# AFT05MS004.net
KiCad netlist of a schematic drawn in Altium Designer
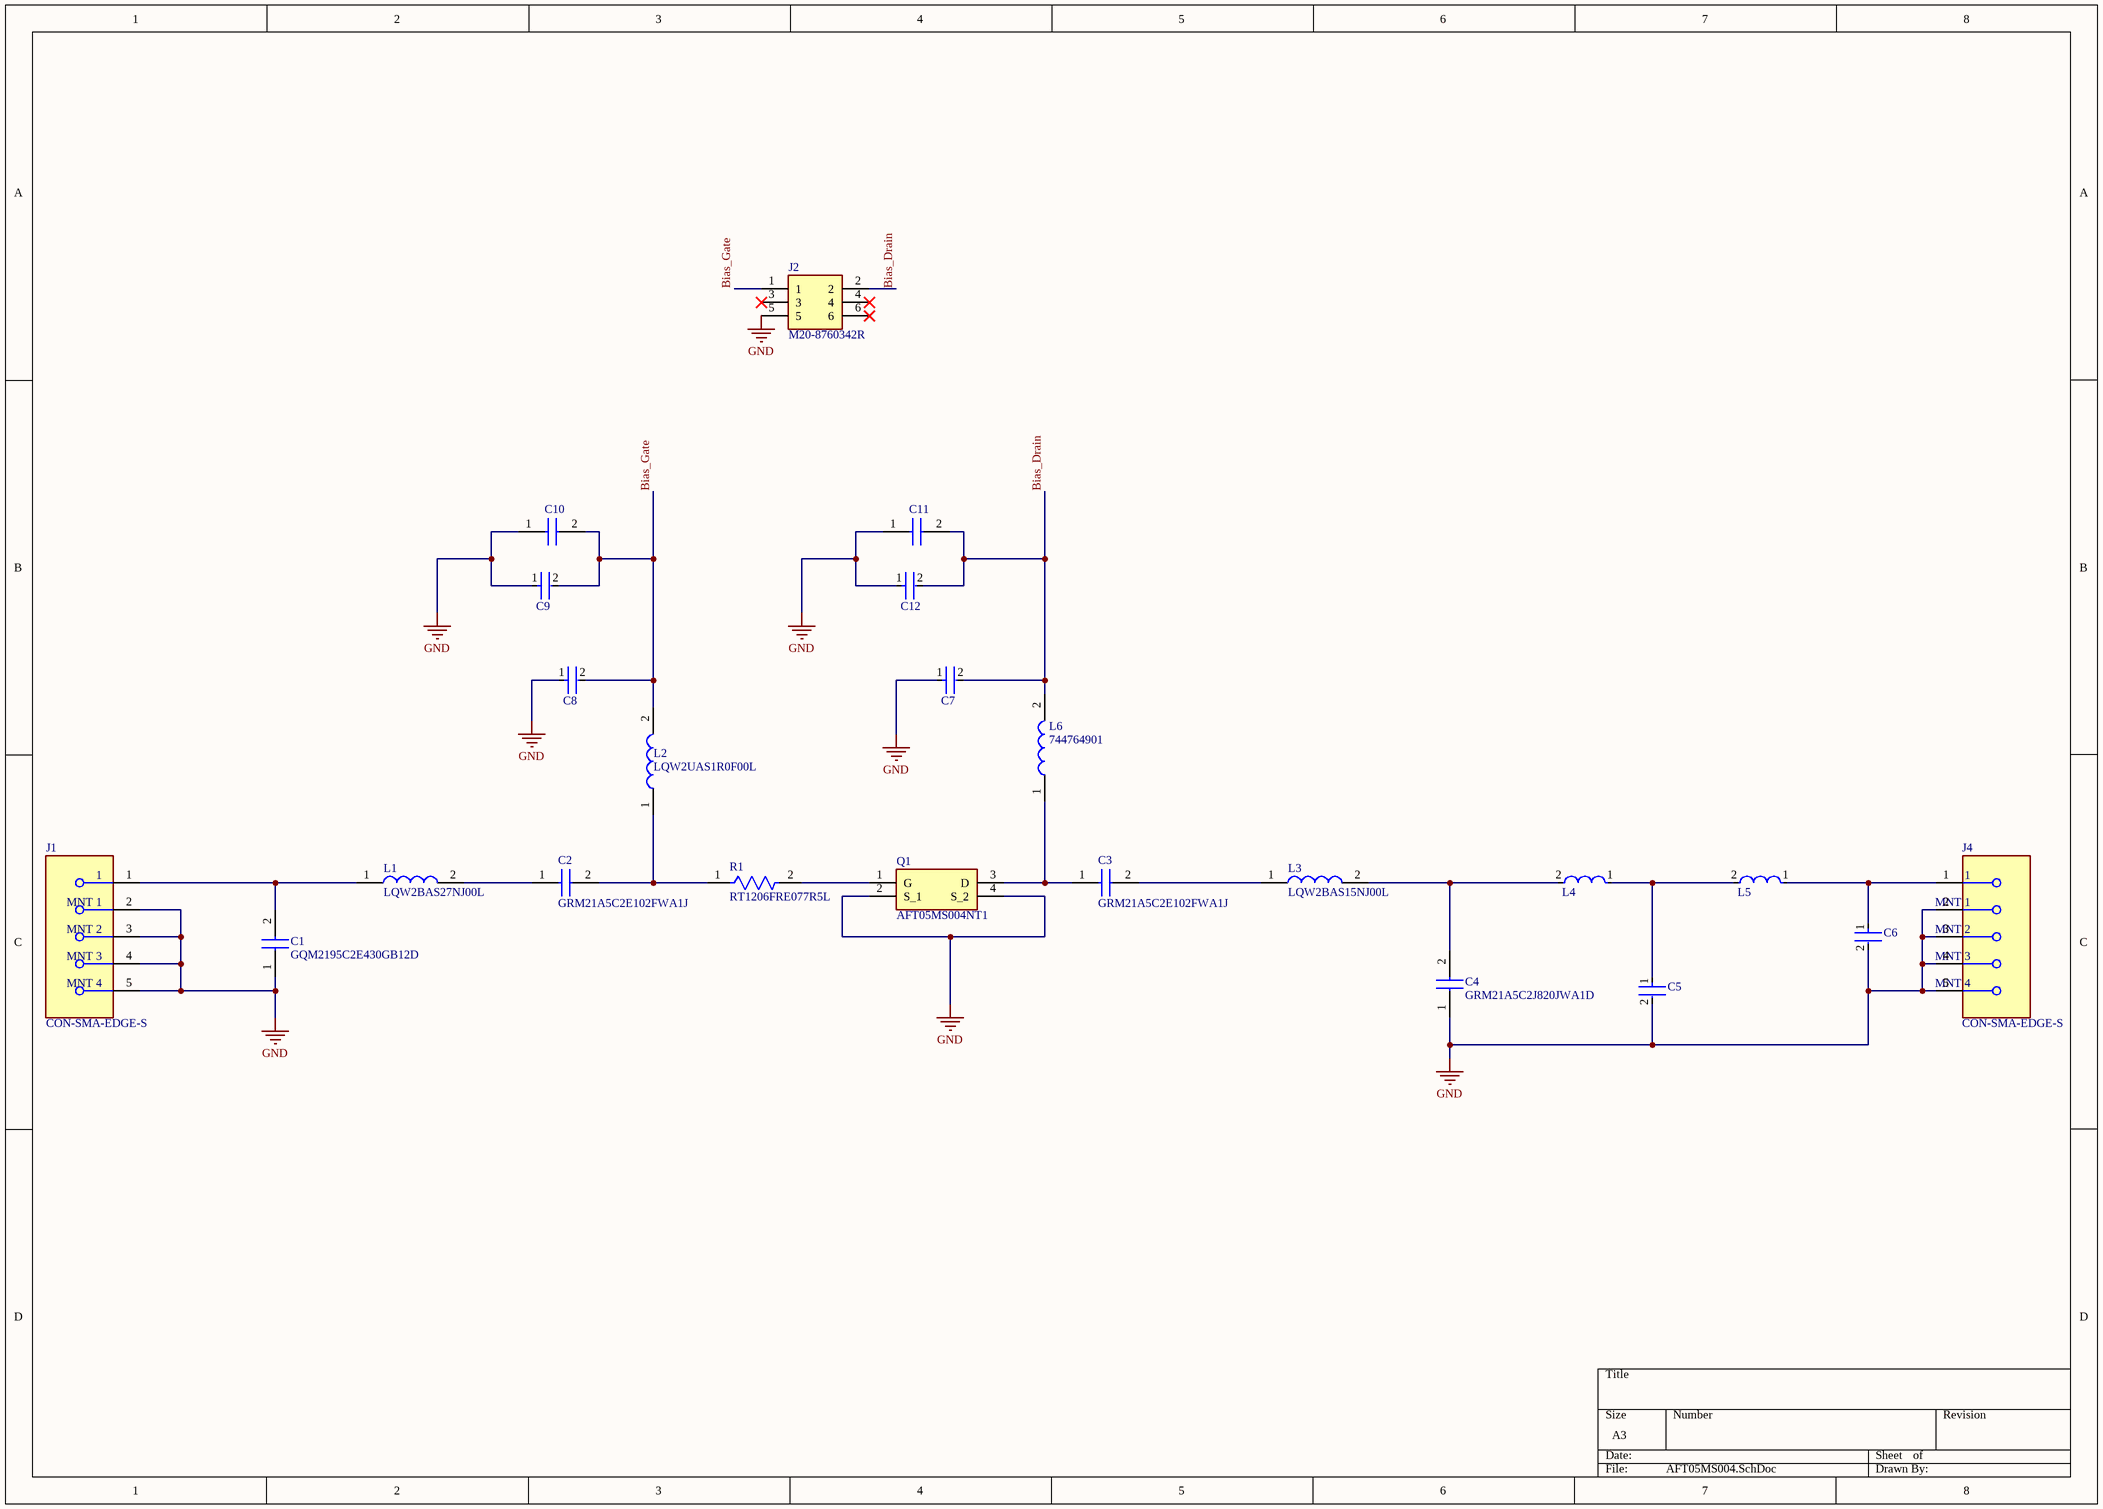
[diagram p0: AFT05MS004.SchDoc]

(export (version "E")
  (design (tool "Eeschema 10.0.6"))
  (components
    (comp (ref "C1")
      (value "GQM2195C2E430GB12D")
      (footprint "SamacSys:GQM2195C2E100GB12D")
      (description "Capacitor")
      (libsource (lib "*") (part "GQM2195C2E430GB12D"))
    )
    (comp (ref "C2")
      (value "GRM21A5C2E102FWA1J")
      (footprint "SamacSys:GRM21x")
      (description "Capacitor")
      (fields (field (name "MOUSER PART NUMBER") "81-GRM21A5C2E102FWA1"))
      (libsource (lib "*") (part "GRM21A5C2E102FWA1J"))
    )
    (comp (ref "C3")
      (value "GRM21A5C2E102FWA1J")
      (footprint "SamacSys:GRM21x")
      (description "Capacitor")
      (fields (field (name "MOUSER PART NUMBER") "81-GRM21A5C2E102FWA1"))
      (libsource (lib "*") (part "GRM21A5C2E102FWA1J"))
    )
    (comp (ref "C4")
      (value "GRM21A5C2J820JWA1D")
      (footprint "SamacSys:GRM21x")
      (description "Capacitor")
      (libsource (lib "*") (part "GRM21A5C2J820JWA1D"))
    )
    (comp (ref "C5")
      (value "GRM21A5C2E390FW01D")
      (footprint "FP-GRM21A-0_2-MFG")
      (description "Chip Multilayer Ceramic Capacitors for General Purpose, 0805, 1000pF, C0G, 30ppm/°C, 1%, 250V")
      (libsource (lib "Altium Content Vault") (part "02cd4be3c70576c341d710602a673aa"))
    )
    (comp (ref "C6")
      (value "GQM2195C2E300GB12D")
      (footprint "FP-GRM21A-0_2-MFG")
      (description "Chip Multilayer Ceramic Capacitors for General Purpose, 0805, 1000pF, C0G, 30ppm/°C, 1%, 250V")
      (libsource (lib "Altium Content Vault") (part "02cd4be3c70576c341d710602a673aa"))
    )
    (comp (ref "C7")
      (value "GQM2195C2E300GB12D")
      (footprint "FP-GRM21A-0_2-MFG")
      (description "Chip Multilayer Ceramic Capacitors for General Purpose, 0805, 1000pF, C0G, 30ppm/°C, 1%, 250V")
      (libsource (lib "Altium Content Vault") (part "02cd4be3c70576c341d710602a673aa"))
    )
    (comp (ref "C8")
      (value "GQM2195C2E300GB12D")
      (footprint "FP-GRM21A-0_2-MFG")
      (description "Chip Multilayer Ceramic Capacitors for General Purpose, 0805, 1000pF, C0G, 30ppm/°C, 1%, 250V")
      (libsource (lib "Altium Content Vault") (part "02cd4be3c70576c341d710602a673aa"))
    )
    (comp (ref "C9")
      (value "GRM21A5C2E102FWA1J")
      (footprint "FP-GRM21A-0_2-MFG")
      (description "Chip Multilayer Ceramic Capacitors for General Purpose, 0805, 1000pF, C0G, 30ppm/°C, 1%, 250V")
      (libsource (lib "Altium Content Vault") (part "02cd4be3c70576c341d710602a673aa"))
    )
    (comp (ref "C10")
      (value "GJ821BR71H105KA12K")
      (footprint "SamacSys:CAPC2012X135N")
      (description "Capacitor")
      (fields (field (name "MOUSER PART NUMBER") "81-GJ821BR71H105KA2K"))
      (libsource (lib "*") (part "GJ821BR71H105KA12K"))
    )
    (comp (ref "C11")
      (value "GJ821BR71H105KA12K")
      (footprint "SamacSys:CAPC2012X135N")
      (description "Capacitor")
      (fields (field (name "MOUSER PART NUMBER") "81-GJ821BR71H105KA2K"))
      (libsource (lib "*") (part "GJ821BR71H105KA12K"))
    )
    (comp (ref "C12")
      (value "GRM21A5C2E102FWA1J")
      (footprint "FP-GRM21A-0_2-MFG")
      (description "Chip Multilayer Ceramic Capacitors for General Purpose, 0805, 1000pF, C0G, 30ppm/°C, 1%, 250V")
      (libsource (lib "Altium Content Vault") (part "02cd4be3c70576c341d710602a673aa"))
    )
    (comp (ref "J1")
      (value "CON-SMA-EDGE-S")
      (footprint "FP-CON-SMA-EDGE-S-MFG")
      (description "CONN SMA JACK STR EDGE MNT")
      (fields
        (field (name "OCTOPART") "https://octopart.com/con-sma-edge-s-rf+solutions-70967450")
        (field (name "MANUFACTURER") "RF Solutions Ltd.")
      )
      (libsource (lib "Altium Content Vault") (part "a163d97a771fcdd2fd1f1a9264c171f"))
    )
    (comp (ref "J2")
      (value "M20-8760342R")
      (footprint "SamacSys:M208760342R")
      (description "Connector")
      (fields (field (name "MOUSER PART NUMBER") "855-M20-8760342R"))
      (libsource (lib "*") (part "M20-8760342R"))
    )
    (comp (ref "J4")
      (value "CON-SMA-EDGE-S")
      (footprint "FP-CON-SMA-EDGE-S-MFG")
      (description "CONN SMA JACK STR EDGE MNT")
      (fields
        (field (name "OCTOPART") "https://octopart.com/con-sma-edge-s-rf+solutions-70967450")
        (field (name "MANUFACTURER") "RF Solutions Ltd.")
      )
      (libsource (lib "") (part "a163d97a771fcdd2fd1f1a9264c171f_1"))
    )
    (comp (ref "L1")
      (value "LQW2BAS27NJ00L")
      (footprint "SamacSys:LQW2BAN11NG00L")
      (description "Inductor")
      (fields (field (name "MOUSER PART NUMBER") "81-LQW2BAS27NJ00L"))
      (libsource (lib "*") (part "LQW2BAS27NJ00L"))
    )
    (comp (ref "L2")
      (value "LQW2UAS1R0F00L")
      (footprint "SamacSys:LQW2UAS12NG00L")
      (description "Inductor")
      (fields (field (name "MOUSER PART NUMBER") "81-LQW2UAS1R0F00L"))
      (libsource (lib "*") (part "LQW2UAS1R0F00L"))
    )
    (comp (ref "L3")
      (value "LQW2BAS15NJ00L")
      (footprint "SamacSys:LQW2BAN11NG00L")
      (description "Inductor")
      (fields
        (field (name "MANUFACTURER_PART_NUMBER") "LQW2BAS18NJ00L")
        (field (name "MOUSER PART NUMBER") "81-LQW2BAS18NJ00L")
      )
      (libsource (lib "*") (part "LQW2BAS18NJ00L"))
    )
    (comp (ref "L4")
      (value "LQW2BAS56NG00L")
      (footprint "FP-LQW2BAN_00-MFG")
      (description "Wire Wound RF Inductor 56nH ±2% 500mA 0.34Ω 0805 (2015)")
      (fields (field (name "TOLERANCE") "2%"))
      (libsource (lib "Altium Content Vault") (part "725321dda6339637d4d059423bc1c3c"))
    )
    (comp (ref "L5")
      (value "LQW2BAS56NG00L")
      (footprint "FP-LQW2BAN_00-MFG")
      (description "Wire Wound RF Inductor 56nH ±2% 500mA 0.34Ω 0805 (2015)")
      (fields (field (name "TOLERANCE") "2%"))
      (libsource (lib "Altium Content Vault") (part "725321dda6339637d4d059423bc1c3c"))
    )
    (comp (ref "L6")
      (value "744764901")
      (footprint "SamacSys:INDM3425X240N")
      (description "Inductor")
      (fields (field (name "MOUSER PART NUMBER") "710-744764901"))
      (libsource (lib "*") (part "744764901"))
    )
    (comp (ref "Q1")
      (value "AFT05MS004NT1")
      (footprint "SamacSys:MMG38151BT1")
      (description "MOSFET (N-Channel)")
      (fields (field (name "MOUSER PART NUMBER") "841-AFT05MS004NT1"))
      (libsource (lib "*") (part "AFT05MS004NT1"))
    )
    (comp (ref "R1")
      (value "RT1206FRE077R5L")
      (footprint "FP-RT1206-MFG")
      (description "RES SMD 7.5 OHM 1% 1/4W 1206")
      (fields
        (field (name "OCTOPART") "https://octopart.com/rt1206fre077r5l-yageo-71404764")
        (field (name "TOLERANCE") "0.0002")
      )
      (libsource (lib "Altium Content Vault") (part "1029c3af85768c4190bb7ad29bc67b5"))
    )
  )
  (nets
    (net (code "1") (name "/Bias_Drain") (class "Default")
      (node (ref "C11") (pin "2") (pinfunction "2_2") (pintype "passive"))
      (node (ref "C12") (pin "2") (pinfunction "2_2") (pintype "passive"))
      (node (ref "C7") (pin "2") (pinfunction "2_2") (pintype "passive"))
      (node (ref "J2") (pin "2") (pinfunction "2_2") (pintype "passive"))
      (node (ref "L6") (pin "2") (pinfunction "2_2") (pintype "passive"))
    )
    (net (code "2") (name "/Bias_Gate") (class "Default")
      (node (ref "C10") (pin "2") (pinfunction "2_2") (pintype "passive"))
      (node (ref "C8") (pin "2") (pinfunction "2_2") (pintype "passive"))
      (node (ref "C9") (pin "2") (pinfunction "2_2") (pintype "passive"))
      (node (ref "J2") (pin "1") (pinfunction "1_1") (pintype "passive"))
      (node (ref "L2") (pin "2") (pinfunction "2_2") (pintype "passive"))
    )
    (net (code "3") (name "GND") (class "Default")
      (node (ref "C1") (pin "1") (pinfunction "1_1") (pintype "passive"))
      (node (ref "C10") (pin "1") (pinfunction "1_1") (pintype "passive"))
      (node (ref "C11") (pin "1") (pinfunction "1_1") (pintype "passive"))
      (node (ref "C12") (pin "1") (pinfunction "1_1") (pintype "passive"))
      (node (ref "C4") (pin "1") (pinfunction "1_1") (pintype "passive"))
      (node (ref "C5") (pin "2") (pinfunction "2_2") (pintype "passive"))
      (node (ref "C6") (pin "2") (pinfunction "2_2") (pintype "passive"))
      (node (ref "C7") (pin "1") (pinfunction "1_1") (pintype "passive"))
      (node (ref "C8") (pin "1") (pinfunction "1_1") (pintype "passive"))
      (node (ref "C9") (pin "1") (pinfunction "1_1") (pintype "passive"))
      (node (ref "J1") (pin "2") (pinfunction "MNT_1_2") (pintype "passive"))
      (node (ref "J1") (pin "3") (pinfunction "MNT_2_3") (pintype "passive"))
      (node (ref "J1") (pin "4") (pinfunction "MNT_3_4") (pintype "passive"))
      (node (ref "J1") (pin "5") (pinfunction "MNT_4_5") (pintype "passive"))
      (node (ref "J2") (pin "5") (pinfunction "5_5") (pintype "passive"))
      (node (ref "J4") (pin "2") (pinfunction "MNT_1_2") (pintype "passive"))
      (node (ref "J4") (pin "3") (pinfunction "MNT_2_3") (pintype "passive"))
      (node (ref "J4") (pin "4") (pinfunction "MNT_3_4") (pintype "passive"))
      (node (ref "J4") (pin "5") (pinfunction "MNT_4_5") (pintype "passive"))
      (node (ref "Q1") (pin "2") (pinfunction "S_1_2") (pintype "passive"))
      (node (ref "Q1") (pin "4") (pinfunction "S_2_4") (pintype "passive"))
    )
    (net (code "4") (name "Net-(C1-Pad2)") (class "Default")
      (node (ref "C1") (pin "2") (pinfunction "2_2") (pintype "passive"))
      (node (ref "J1") (pin "1") (pinfunction "1_1") (pintype "passive"))
      (node (ref "L1") (pin "1") (pinfunction "1_1") (pintype "passive"))
    )
    (net (code "5") (name "Net-(C2-Pad1)") (class "Default")
      (node (ref "C2") (pin "1") (pinfunction "1_1") (pintype "passive"))
      (node (ref "L1") (pin "2") (pinfunction "2_2") (pintype "passive"))
    )
    (net (code "6") (name "Net-(C2-Pad2)") (class "Default")
      (node (ref "C2") (pin "2") (pinfunction "2_2") (pintype "passive"))
      (node (ref "L2") (pin "1") (pinfunction "1_1") (pintype "passive"))
      (node (ref "R1") (pin "1") (pinfunction "1_1") (pintype "passive"))
    )
    (net (code "7") (name "Net-(C3-Pad2)") (class "Default")
      (node (ref "C3") (pin "2") (pinfunction "2_2") (pintype "passive"))
      (node (ref "L3") (pin "1") (pinfunction "1_1") (pintype "passive"))
    )
    (net (code "8") (name "Net-(C4-Pad2)") (class "Default")
      (node (ref "C4") (pin "2") (pinfunction "2_2") (pintype "passive"))
      (node (ref "L3") (pin "2") (pinfunction "2_2") (pintype "passive"))
      (node (ref "L4") (pin "2") (pinfunction "2_2") (pintype "passive"))
    )
    (net (code "9") (name "Net-(C5-Pad1)") (class "Default")
      (node (ref "C5") (pin "1") (pinfunction "1_1") (pintype "passive"))
      (node (ref "L4") (pin "1") (pinfunction "1_1") (pintype "passive"))
      (node (ref "L5") (pin "2") (pinfunction "2_2") (pintype "passive"))
    )
    (net (code "10") (name "Net-(C6-Pad1)") (class "Default")
      (node (ref "C6") (pin "1") (pinfunction "1_1") (pintype "passive"))
      (node (ref "J4") (pin "1") (pinfunction "1_1") (pintype "passive"))
      (node (ref "L5") (pin "1") (pinfunction "1_1") (pintype "passive"))
    )
    (net (code "11") (name "Net-(Q1-D)") (class "Default")
      (node (ref "C3") (pin "1") (pinfunction "1_1") (pintype "passive"))
      (node (ref "L6") (pin "1") (pinfunction "1_1") (pintype "passive"))
      (node (ref "Q1") (pin "3") (pinfunction "D_3") (pintype "passive"))
    )
    (net (code "12") (name "Net-(Q1-G)") (class "Default")
      (node (ref "Q1") (pin "1") (pinfunction "G_1") (pintype "passive"))
      (node (ref "R1") (pin "2") (pinfunction "2_2") (pintype "passive"))
    )
    (net (code "13") (name "unconnected-(J2-Pad3)") (class "Default")
      (node (ref "J2") (pin "3") (pinfunction "3_3") (pintype "passive+no_connect"))
    )
    (net (code "14") (name "unconnected-(J2-Pad4)") (class "Default")
      (node (ref "J2") (pin "4") (pinfunction "4_4") (pintype "passive+no_connect"))
    )
    (net (code "15") (name "unconnected-(J2-Pad6)") (class "Default")
      (node (ref "J2") (pin "6") (pinfunction "6_6") (pintype "passive+no_connect"))
    )
  )
)
